# 03_GateDriver.net
KiCad netlist of a schematic drawn in Altium Designer
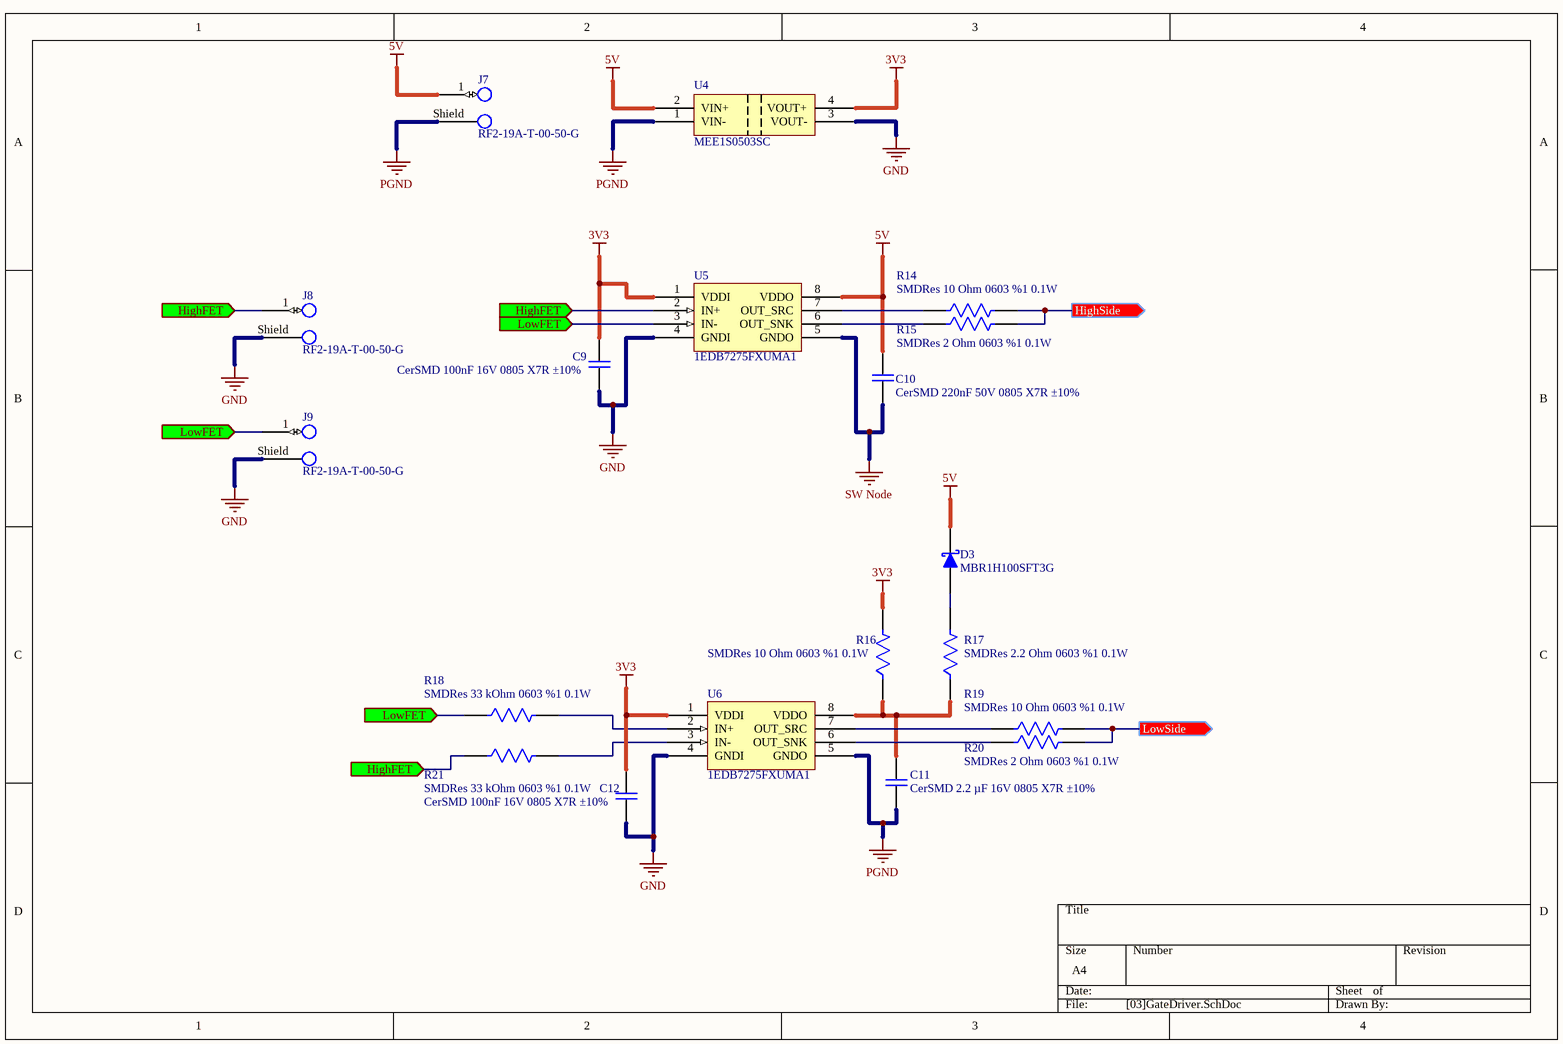
[diagram p0: [03]GateDriver.SchDoc]

(export (version "E")
  (design (tool "Eeschema 10.0.6"))
  (components
    (comp (ref "C9")
      (value "CerSMD 100nF 16V 0805 X7R ±10%")
      (footprint "CAPC2012X09N")
      (description "Ceramic Capacitor SMD 100nF 10V 0805 X7R ±10%")
      (fields (field (name "MOUSER PART NUMBER") "710-885012207016") (field (name "VOLTAGE") "10V"))
      (libsource (lib "AGH Power Electronics Lab") (part "100 nF"))
    )
    (comp (ref "C10")
      (value "CerSMD 220nF 50V 0805 X7R ±10%")
      (footprint "CAPC2012X09N")
      (description "Ceramic Capacitor SMD 220nF 50V 0805 X7R ±10%")
      (fields (field (name "TOLERANCE") "±10%") (field (name "MOUSER PART NUMBER") "81-GRM40X7R224K050AL"))
      (libsource (lib "AGH Power Electronics Lab") (part "220nF"))
    )
    (comp (ref "C11")
      (value "CerSMD 2.2 µF 16V 0805 X7R ±10%")
      (footprint "CAPC2012X09N")
      (description "Ceramic Capacitor SMD 2.2 µF 16V 0805 X7R ±10%")
      (fields
        (field (name "FARNELL PART NUMBER") "1907345")
        (field (name "DIGI-KEY PART NUMBER") "445-1420-1-ND")
      )
      (libsource (lib "AGH Power Electronics Lab") (part "2.2 µF"))
    )
    (comp (ref "C12")
      (value "CerSMD 100nF 16V 0805 X7R ±10%")
      (footprint "CAPC2012X09N")
      (description "Ceramic Capacitor SMD 100nF 10V 0805 X7R ±10%")
      (fields (field (name "MOUSER PART NUMBER") "710-885012207016") (field (name "VOLTAGE") "10V"))
      (libsource (lib "AGH Power Electronics Lab") (part "100 nF"))
    )
    (comp (ref "D3")
      (value "MBR1H100SFT3G")
      (footprint "SODFL360X95-2N")
      (libsource (lib "AGH Power Electronics Lab") (part "ONSC-D-K1A2-2_A"))
    )
    (comp (ref "J7")
      (value "RF2-19A-T-00-50-G")
      (footprint "RF2-19A-T-00-50-G")
      (description "Rf Sma Connector")
      (libsource (lib "AGH Power Electronics Lab") (part "RF2-19A-T-00-50-G"))
    )
    (comp (ref "J8")
      (value "RF2-19A-T-00-50-G")
      (footprint "RF2-19A-T-00-50-G")
      (description "Rf Sma Connector")
      (libsource (lib "AGH Power Electronics Lab") (part "RF2-19A-T-00-50-G"))
    )
    (comp (ref "J9")
      (value "RF2-19A-T-00-50-G")
      (footprint "RF2-19A-T-00-50-G")
      (description "Rf Sma Connector")
      (libsource (lib "AGH Power Electronics Lab") (part "RF2-19A-T-00-50-G"))
    )
    (comp (ref "R14")
      (value "SMDRes 10 Ohm 0603 %1 0.1W")
      (footprint "RESC1508X06N")
      (description "Res Thick Film 0603 10 Ohm Ohm 1% 0.1W(1/10W) ±100ppm/C Pad SMD T/R Automotive AEC-Q200")
      (fields
        (field (name "DIGI-KEY PART NUMBER") "RMCF0603FT10R0CT-ND")
        (field (name "MOUSER PART NUMBER") "708-RMCF0603FT10R0")
      )
      (libsource (lib "AGH Power Electronics Lab") (part "2.2 Ohm"))
    )
    (comp (ref "R15")
      (value "SMDRes 2 Ohm 0603 %1 0.1W")
      (footprint "RESC1508X06N")
      (description "Res Thick Film 0603 2 Ohm Ohm 1% 0.1W(1/10W) ±100ppm/C Pad SMD T/R Automotive AEC-Q200")
      (fields (field (name "MANUFACTURER") "Stackpole Electronics Inc") (field (name "POWER") "0.1W"))
      (libsource (lib "AGH Power Electronics Lab") (part "2.2 Ohm"))
    )
    (comp (ref "R16")
      (value "SMDRes 10 Ohm 0603 %1 0.1W")
      (footprint "RESC1508X06N")
      (description "Res Thick Film 0603 10 Ohm Ohm 1% 0.1W(1/10W) ±100ppm/C Pad SMD T/R Automotive AEC-Q200")
      (fields
        (field (name "DIGI-KEY PART NUMBER") "RMCF0603FT10R0CT-ND")
        (field (name "MOUSER PART NUMBER") "708-RMCF0603FT10R0")
      )
      (libsource (lib "AGH Power Electronics Lab") (part "2.2 Ohm"))
    )
    (comp (ref "R17")
      (value "SMDRes 2.2 Ohm 0603 %1 0.1W")
      (footprint "RESC1508X06N")
      (description "Res Thick Film 0603 2.2 Ohm Ohm 1% 0.1W(1/10W) ±100ppm/C Pad SMD T/R Automotive AEC-Q200")
      (fields (field (name "MOUSER PART NUMBER") "708-RMCF0603FT2R20") (field (name "POWER") "0.1W"))
      (libsource (lib "AGH Power Electronics Lab") (part "2.2 Ohm"))
    )
    (comp (ref "R18")
      (value "SMDRes 33 kOhm 0603 %1 0.1W")
      (footprint "RESC1508X06N")
      (description "Res Thick Film 0603 33 kOhm Ohm 1% 0.1W(1/10W) ±100ppm/C Pad SMD T/R Automotive AEC-Q200")
      (fields (field (name "TOLERANCE") "±1%") (field (name "DIGI-KEY PART NUMBER") "RMCF0603FT33K0CT-ND"))
      (libsource (lib "AGH Power Electronics Lab") (part "2.2 Ohm"))
    )
    (comp (ref "R19")
      (value "SMDRes 10 Ohm 0603 %1 0.1W")
      (footprint "RESC1508X06N")
      (description "Res Thick Film 0603 10 Ohm Ohm 1% 0.1W(1/10W) ±100ppm/C Pad SMD T/R Automotive AEC-Q200")
      (fields
        (field (name "DIGI-KEY PART NUMBER") "RMCF0603FT10R0CT-ND")
        (field (name "MOUSER PART NUMBER") "708-RMCF0603FT10R0")
      )
      (libsource (lib "AGH Power Electronics Lab") (part "2.2 Ohm"))
    )
    (comp (ref "R20")
      (value "SMDRes 2 Ohm 0603 %1 0.1W")
      (footprint "RESC1508X06N")
      (description "Res Thick Film 0603 2 Ohm Ohm 1% 0.1W(1/10W) ±100ppm/C Pad SMD T/R Automotive AEC-Q200")
      (fields (field (name "MANUFACTURER") "Stackpole Electronics Inc") (field (name "POWER") "0.1W"))
      (libsource (lib "AGH Power Electronics Lab") (part "2.2 Ohm"))
    )
    (comp (ref "R21")
      (value "SMDRes 33 kOhm 0603 %1 0.1W")
      (footprint "RESC1508X06N")
      (description "Res Thick Film 0603 33 kOhm Ohm 1% 0.1W(1/10W) ±100ppm/C Pad SMD T/R Automotive AEC-Q200")
      (fields (field (name "TOLERANCE") "±1%") (field (name "DIGI-KEY PART NUMBER") "RMCF0603FT33K0CT-ND"))
      (libsource (lib "AGH Power Electronics Lab") (part "2.2 Ohm"))
    )
    (comp (ref "U4")
      (value "MEE1S0503SC")
      (footprint "MEE1S0503SC-Footprint-1")
      (description "Murata Power - 5V to 3.3V Isolated DC-DC Converter 1W")
      (libsource (lib "AGH Power Electronics Lab") (part "MEE1S0503SC-Symbol-1"))
    )
    (comp (ref "U5")
      (value "1EDB7275FXUMA1")
      (footprint "SOIC127P600X175-8N")
      (libsource (lib "AGH Power Electronics Lab") (part "1EDB7275FXUMA1"))
    )
    (comp (ref "U6")
      (value "1EDB7275FXUMA1")
      (footprint "SOIC127P600X175-8N")
      (libsource (lib "AGH Power Electronics Lab") (part "1EDB7275FXUMA1"))
    )
  )
  (nets
    (net (code "1") (name "/HighFET") (class "Default")
      (node (ref "J8") (pin "1") (pinfunction "1_1") (pintype "bidirectional"))
      (node (ref "R21") (pin "1") (pinfunction "1_1") (pintype "passive"))
      (node (ref "U5") (pin "2") (pinfunction "IN+_2") (pintype "input"))
    )
    (net (code "2") (name "/HighSide") (class "Default")
      (node (ref "R14") (pin "2") (pinfunction "2_2") (pintype "passive"))
      (node (ref "R15") (pin "2") (pinfunction "2_2") (pintype "passive"))
    )
    (net (code "3") (name "/LowFET") (class "Default")
      (node (ref "J9") (pin "1") (pinfunction "1_1") (pintype "bidirectional"))
      (node (ref "R18") (pin "1") (pinfunction "1_1") (pintype "passive"))
      (node (ref "U5") (pin "3") (pinfunction "IN-_3") (pintype "input"))
    )
    (net (code "4") (name "/LowSide") (class "Default")
      (node (ref "R19") (pin "2") (pinfunction "2_2") (pintype "passive"))
      (node (ref "R20") (pin "2") (pinfunction "2_2") (pintype "passive"))
    )
    (net (code "5") (name "3V3") (class "Default")
      (node (ref "C12") (pin "1") (pinfunction "1_1") (pintype "passive"))
      (node (ref "C9") (pin "1") (pinfunction "1_1") (pintype "passive"))
      (node (ref "R16") (pin "2") (pinfunction "2_2") (pintype "passive"))
      (node (ref "U4") (pin "4") (pinfunction "VOUT+_4") (pintype "power_in"))
      (node (ref "U5") (pin "1") (pinfunction "VDDI_1") (pintype "power_in"))
      (node (ref "U6") (pin "1") (pinfunction "VDDI_1") (pintype "power_in"))
    )
    (net (code "6") (name "5V") (class "Default")
      (node (ref "C10") (pin "1") (pinfunction "1_1") (pintype "passive"))
      (node (ref "D3") (pin "2") (pinfunction "K_2") (pintype "passive"))
      (node (ref "J7") (pin "1") (pinfunction "1_1") (pintype "bidirectional"))
      (node (ref "U4") (pin "2") (pinfunction "VIN+_2") (pintype "power_in"))
      (node (ref "U5") (pin "8") (pinfunction "VDDO_8") (pintype "power_in"))
    )
    (net (code "7") (name "GND") (class "Default")
      (node (ref "C12") (pin "2") (pinfunction "2_2") (pintype "passive"))
      (node (ref "C9") (pin "2") (pinfunction "2_2") (pintype "passive"))
      (node (ref "J8") (pin "Shield") (pinfunction "Shield_Shield") (pintype "power_in"))
      (node (ref "J9") (pin "Shield") (pinfunction "Shield_Shield") (pintype "power_in"))
      (node (ref "U4") (pin "3") (pinfunction "VOUT-_3") (pintype "power_in"))
      (node (ref "U5") (pin "4") (pinfunction "GNDI_4") (pintype "power_in"))
      (node (ref "U6") (pin "4") (pinfunction "GNDI_4") (pintype "power_in"))
    )
    (net (code "8") (name "Net-(D3-A)") (class "Default")
      (node (ref "D3") (pin "1") (pinfunction "A_1") (pintype "passive"))
      (node (ref "R17") (pin "2") (pinfunction "2_2") (pintype "passive"))
    )
    (net (code "9") (name "Net-(U5-OUT_SNK)") (class "Default")
      (node (ref "R15") (pin "1") (pinfunction "1_1") (pintype "passive"))
      (node (ref "U5") (pin "6") (pinfunction "OUT_SNK_6") (pintype "passive"))
    )
    (net (code "10") (name "Net-(U5-OUT_SRC)") (class "Default")
      (node (ref "R14") (pin "1") (pinfunction "1_1") (pintype "passive"))
      (node (ref "U5") (pin "7") (pinfunction "OUT_SRC_7") (pintype "passive"))
    )
    (net (code "11") (name "Net-(U6-IN+)") (class "Default")
      (node (ref "R18") (pin "2") (pinfunction "2_2") (pintype "passive"))
      (node (ref "U6") (pin "2") (pinfunction "IN+_2") (pintype "input"))
    )
    (net (code "12") (name "Net-(U6-IN-)") (class "Default")
      (node (ref "R21") (pin "2") (pinfunction "2_2") (pintype "passive"))
      (node (ref "U6") (pin "3") (pinfunction "IN-_3") (pintype "input"))
    )
    (net (code "13") (name "Net-(U6-OUT_SNK)") (class "Default")
      (node (ref "R20") (pin "1") (pinfunction "1_1") (pintype "passive"))
      (node (ref "U6") (pin "6") (pinfunction "OUT_SNK_6") (pintype "passive"))
    )
    (net (code "14") (name "Net-(U6-OUT_SRC)") (class "Default")
      (node (ref "R19") (pin "1") (pinfunction "1_1") (pintype "passive"))
      (node (ref "U6") (pin "7") (pinfunction "OUT_SRC_7") (pintype "passive"))
    )
    (net (code "15") (name "Net-(U6-VDDO)") (class "Default")
      (node (ref "C11") (pin "1") (pinfunction "1_1") (pintype "passive"))
      (node (ref "R16") (pin "1") (pinfunction "1_1") (pintype "passive"))
      (node (ref "R17") (pin "1") (pinfunction "1_1") (pintype "passive"))
      (node (ref "U6") (pin "8") (pinfunction "VDDO_8") (pintype "power_in"))
    )
    (net (code "16") (name "PGND") (class "Default")
      (node (ref "C11") (pin "2") (pinfunction "2_2") (pintype "passive"))
      (node (ref "J7") (pin "Shield") (pinfunction "Shield_Shield") (pintype "power_in"))
      (node (ref "U4") (pin "1") (pinfunction "VIN-_1") (pintype "power_in"))
      (node (ref "U6") (pin "5") (pinfunction "GNDO_5") (pintype "power_in"))
    )
    (net (code "17") (name "SW Node") (class "Default")
      (node (ref "C10") (pin "2") (pinfunction "2_2") (pintype "passive"))
      (node (ref "U5") (pin "5") (pinfunction "GNDO_5") (pintype "power_in"))
    )
  )
)
